# hallsensing.net
KiCad netlist of a schematic drawn in Altium Designer
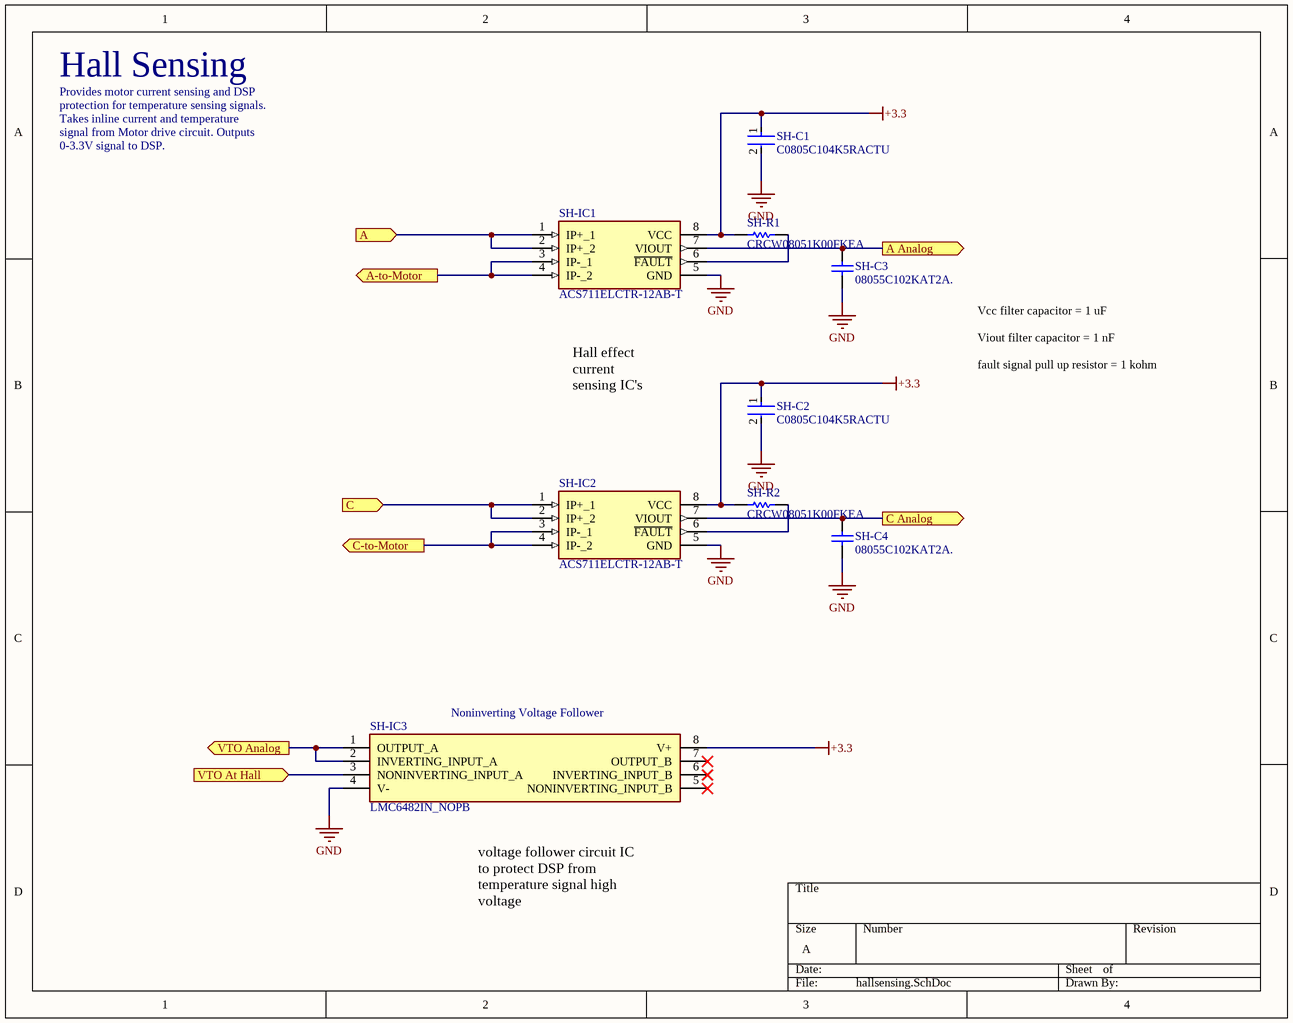
[diagram p0: hallsensing.SchDoc]

(export (version "E")
  (design (tool "Eeschema 10.0.6"))
  (components
    (comp (ref "SH-C1")
      (value "C0805C104K5RACTU")
      (footprint "FP-C0805C-DN-MFG")
      (description "CAP CER 0.1UF 50V X7R 0805")
      (fields
        (field (name "MANUFACTURER") "KEMET")
        (field (name "OCTOPART") "https://octopart.com/c0805c104k5ractu-kemet-143926")
      )
      (libsource (lib "Altium Content Vault") (part "b4654b650e69147ec39a6b967a45e02"))
    )
    (comp (ref "SH-C2")
      (value "C0805C104K5RACTU")
      (footprint "FP-C0805C-DN-MFG")
      (description "CAP CER 0.1UF 50V X7R 0805")
      (fields
        (field (name "MANUFACTURER") "KEMET")
        (field (name "OCTOPART") "https://octopart.com/c0805c104k5ractu-kemet-143926")
      )
      (libsource (lib "Altium Content Vault") (part "b4654b650e69147ec39a6b967a45e02"))
    )
    (comp (ref "SH-C3")
      (value "08055C102KAT2A.")
      (footprint "CAPC2013X94X50ML20T25")
      (fields (field (name "MANUFACTURER") "AVX Interconnect / Elco"))
      (libsource (lib "Altium Content Vault") (part "CAP"))
    )
    (comp (ref "SH-C4")
      (value "08055C102KAT2A.")
      (footprint "CAPC2013X94X50ML20T25")
      (fields (field (name "MANUFACTURER") "AVX Interconnect / Elco"))
      (libsource (lib "Altium Content Vault") (part "CAP"))
    )
    (comp (ref "SH-IC1")
      (value "ACS711ELCTR-12AB-T")
      (footprint "SamacSys:SOIC127P600X175-8N")
      (description "12A current sensing Integrated Circuit")
      (libsource (lib "*") (part "ACS711ELCTR-12AB-T"))
    )
    (comp (ref "SH-IC2")
      (value "ACS711ELCTR-12AB-T")
      (footprint "SamacSys:SOIC127P600X175-8N")
      (description "12A current sensing Integrated Circuit")
      (libsource (lib "*") (part "ACS711ELCTR-12AB-T"))
    )
    (comp (ref "SH-IC3")
      (value "LMC6482IN_NOPB")
      (footprint "SamacSys:DIP794W53P254L959H508Q8N")
      (description "OP-AMP voltage follower Integrated Circuit")
      (fields
        (field (name "MANUFACTURER_PART_NUMBER") "LMC6482IN/NOPB")
        (field (name "MOUSER PART NUMBER") "926-LMC6482IN/NOPB")
      )
      (libsource (lib "*") (part "LMC6482IN_NOPB"))
    )
    (comp (ref "SH-R1")
      (value "CRCW08051K00FKEA")
      (footprint "RESC2013X50X30NL20T20")
      (fields (field (name "MANUFACTURER") "Vishay Dale"))
      (libsource (lib "Altium Content Vault") (part "RES"))
    )
    (comp (ref "SH-R2")
      (value "CRCW08051K00FKEA")
      (footprint "RESC2013X50X30NL20T20")
      (fields (field (name "MANUFACTURER") "Vishay Dale"))
      (libsource (lib "Altium Content Vault") (part "RES"))
    )
  )
  (nets
    (net (code "1") (name "+3.3") (class "Default")
      (node (ref "SH-C1") (pin "1") (pinfunction "1_1") (pintype "passive"))
      (node (ref "SH-C2") (pin "1") (pinfunction "1_1") (pintype "passive"))
      (node (ref "SH-IC1") (pin "8") (pinfunction "VCC_8") (pintype "power_in"))
      (node (ref "SH-IC2") (pin "8") (pinfunction "VCC_8") (pintype "power_in"))
      (node (ref "SH-IC3") (pin "8") (pinfunction "V+_8") (pintype "passive"))
      (node (ref "SH-R1") (pin "1") (pinfunction "1_1") (pintype "passive"))
      (node (ref "SH-R2") (pin "1") (pinfunction "1_1") (pintype "passive"))
    )
    (net (code "2") (name "/A") (class "Default")
      (node (ref "SH-IC1") (pin "1") (pinfunction "IP+_1_1") (pintype "input"))
      (node (ref "SH-IC1") (pin "2") (pinfunction "IP+_2_2") (pintype "input"))
    )
    (net (code "3") (name "/A Analog") (class "Default")
      (node (ref "SH-C3") (pin "2") (pinfunction "2_2") (pintype "passive"))
      (node (ref "SH-IC1") (pin "7") (pinfunction "VIOUT_7") (pintype "output"))
    )
    (net (code "4") (name "/A-to-Motor") (class "Default")
      (node (ref "SH-IC1") (pin "3") (pinfunction "IP-_1_3") (pintype "input"))
      (node (ref "SH-IC1") (pin "4") (pinfunction "IP-_2_4") (pintype "input"))
    )
    (net (code "5") (name "/C") (class "Default")
      (node (ref "SH-IC2") (pin "1") (pinfunction "IP+_1_1") (pintype "input"))
      (node (ref "SH-IC2") (pin "2") (pinfunction "IP+_2_2") (pintype "input"))
    )
    (net (code "6") (name "/C Analog") (class "Default")
      (node (ref "SH-C4") (pin "2") (pinfunction "2_2") (pintype "passive"))
      (node (ref "SH-IC2") (pin "7") (pinfunction "VIOUT_7") (pintype "output"))
    )
    (net (code "7") (name "/C-to-Motor") (class "Default")
      (node (ref "SH-IC2") (pin "3") (pinfunction "IP-_1_3") (pintype "input"))
      (node (ref "SH-IC2") (pin "4") (pinfunction "IP-_2_4") (pintype "input"))
    )
    (net (code "8") (name "/VTO Analog") (class "Default")
      (node (ref "SH-IC3") (pin "1") (pinfunction "OUTPUT_A_1") (pintype "passive"))
      (node (ref "SH-IC3") (pin "2") (pinfunction "INVERTING_INPUT_A_2") (pintype "passive"))
    )
    (net (code "9") (name "/VTO At Hall") (class "Default")
      (node (ref "SH-IC3") (pin "3") (pinfunction "NONINVERTING_INPUT_A_3") (pintype "passive"))
    )
    (net (code "10") (name "GND") (class "Default")
      (node (ref "SH-C1") (pin "2") (pinfunction "2_2") (pintype "passive"))
      (node (ref "SH-C2") (pin "2") (pinfunction "2_2") (pintype "passive"))
      (node (ref "SH-C3") (pin "1") (pinfunction "1_1") (pintype "passive"))
      (node (ref "SH-C4") (pin "1") (pinfunction "1_1") (pintype "passive"))
      (node (ref "SH-IC1") (pin "5") (pinfunction "GND_5") (pintype "power_in"))
      (node (ref "SH-IC2") (pin "5") (pinfunction "GND_5") (pintype "power_in"))
      (node (ref "SH-IC3") (pin "4") (pinfunction "V-_4") (pintype "passive"))
    )
    (net (code "11") (name "Net-(SH-IC1-~{FAULT})") (class "Default")
      (node (ref "SH-IC1") (pin "6") (pinfunction "~{FAULT}_6") (pintype "output"))
      (node (ref "SH-R1") (pin "2") (pinfunction "2_2") (pintype "passive"))
    )
    (net (code "12") (name "Net-(SH-IC2-~{FAULT})") (class "Default")
      (node (ref "SH-IC2") (pin "6") (pinfunction "~{FAULT}_6") (pintype "output"))
      (node (ref "SH-R2") (pin "2") (pinfunction "2_2") (pintype "passive"))
    )
    (net (code "13") (name "unconnected-(SH-IC3-INVERTING_INPUT_B-Pad6)") (class "Default")
      (node (ref "SH-IC3") (pin "6") (pinfunction "INVERTING_INPUT_B_6") (pintype "passive+no_connect"))
    )
    (net (code "14") (name "unconnected-(SH-IC3-NONINVERTING_INPUT_B-Pad5)") (class "Default")
      (node (ref "SH-IC3") (pin "5") (pinfunction "NONINVERTING_INPUT_B_5") (pintype "passive+no_connect"))
    )
    (net (code "15") (name "unconnected-(SH-IC3-OUTPUT_B-Pad7)") (class "Default")
      (node (ref "SH-IC3") (pin "7") (pinfunction "OUTPUT_B_7") (pintype "passive+no_connect"))
    )
  )
)
